# LEDPower.net
KiCad netlist of a schematic drawn in Altium Designer
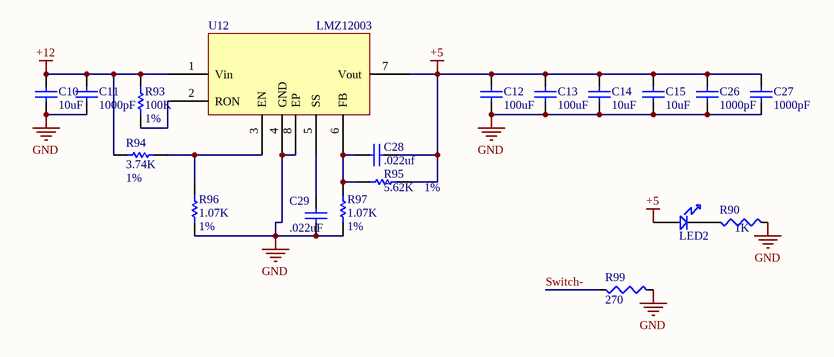
[diagram p0: LEDPower.SchDoc]

(export (version "E")
  (design (tool "Eeschema 10.0.6"))
  (components
    (comp (ref "C10")
      (value "10uF")
      (footprint "PassiveComponents:0805 (2012) Capacitor")
      (description "Capacitor")
      (libsource (lib "PassiveComponents") (part "Capacitor (non-polarized)"))
    )
    (comp (ref "C11")
      (value "1000pF")
      (footprint "PassiveComponents:0805 (2012) Capacitor")
      (description "Capacitor")
      (libsource (lib "PassiveComponents") (part "Capacitor (non-polarized)"))
    )
    (comp (ref "C12")
      (value "100uF")
      (footprint "PassiveComponents:1210 (3225) Capacitor")
      (description "Capacitor")
      (libsource (lib "PassiveComponents") (part "Capacitor (non-polarized)"))
    )
    (comp (ref "C13")
      (value "100uF")
      (footprint "PassiveComponents:1210 (3225) Capacitor")
      (description "Capacitor")
      (libsource (lib "PassiveComponents") (part "Capacitor (non-polarized)"))
    )
    (comp (ref "C14")
      (value "10uF")
      (footprint "PassiveComponents:0805 (2012) Capacitor")
      (description "Capacitor")
      (libsource (lib "PassiveComponents") (part "Capacitor (non-polarized)"))
    )
    (comp (ref "C15")
      (value "10uF")
      (footprint "PassiveComponents:0805 (2012) Capacitor")
      (description "Capacitor")
      (libsource (lib "PassiveComponents") (part "Capacitor (non-polarized)"))
    )
    (comp (ref "C26")
      (value "1000pF")
      (footprint "PassiveComponents:0805 (2012) Capacitor")
      (description "Capacitor")
      (libsource (lib "PassiveComponents") (part "Capacitor (non-polarized)"))
    )
    (comp (ref "C27")
      (value "1000pF")
      (footprint "PassiveComponents:0805 (2012) Capacitor")
      (description "Capacitor")
      (libsource (lib "PassiveComponents") (part "Capacitor (non-polarized)"))
    )
    (comp (ref "C28")
      (value ".022uf")
      (footprint "PassiveComponents:0805 (2012) Capacitor")
      (description "Capacitor")
      (libsource (lib "PassiveComponents") (part "Capacitor (non-polarized)"))
    )
    (comp (ref "C29")
      (value ".022uF")
      (footprint "PassiveComponents:0805 (2012) Capacitor")
      (description "Capacitor")
      (libsource (lib "PassiveComponents") (part "Capacitor (non-polarized)"))
    )
    (comp (ref "LED2")
      (value "LED")
      (footprint "LED 0805")
      (description "Standard LED")
      (libsource (lib "PassiveComponents") (part "LED"))
    )
    (comp (ref "R90")
      (value "1K")
      (footprint "0805 (2012) Capacitor")
      (description "Resistor")
      (libsource (lib "PassiveComponents") (part "Resistor"))
    )
    (comp (ref "R93")
      (value "100K")
      (footprint "R 0805 (2012) RESISTOR")
      (fields (field (name "TOLERANCE") "1%"))
      (libsource (lib "LEDCube") (part "RES 0805 1K 1%"))
    )
    (comp (ref "R94")
      (value "3.74K")
      (footprint "R 0805 (2012) RESISTOR")
      (fields (field (name "TOLERANCE") "1%"))
      (libsource (lib "LEDCube") (part "RES 0805 1K 1%"))
    )
    (comp (ref "R95")
      (value "5.62K")
      (footprint "R 0805 (2012) RESISTOR")
      (fields (field (name "TOLERANCE") "1%"))
      (libsource (lib "LEDCube") (part "RES 0805 1K 1%"))
    )
    (comp (ref "R96")
      (value "1.07K")
      (footprint "R 0805 (2012) RESISTOR")
      (fields (field (name "TOLERANCE") "1%"))
      (libsource (lib "LEDCube") (part "RES 0805 1K 1%"))
    )
    (comp (ref "R97")
      (value "1.07K")
      (footprint "R 0805 (2012) RESISTOR")
      (fields (field (name "TOLERANCE") "1%"))
      (libsource (lib "LEDCube") (part "RES 0805 1K 1%"))
    )
    (comp (ref "R99")
      (value "270")
      (footprint "0805 (2012) Capacitor")
      (description "Resistor")
      (libsource (lib "LEDCube") (part "Resistor"))
    )
    (comp (ref "U12")
      (value "LMZ12003")
      (footprint "7-Lead PFM")
      (libsource (lib "LEDCube") (part "LMZ12003"))
    )
  )
  (nets
    (net (code "1") (name "+5") (class "Default")
      (node (ref "C12") (pin "2") (pinfunction "2_2") (pintype "passive"))
      (node (ref "C13") (pin "2") (pinfunction "2_2") (pintype "passive"))
      (node (ref "C14") (pin "1") (pinfunction "1_1") (pintype "passive"))
      (node (ref "C15") (pin "1") (pinfunction "1_1") (pintype "passive"))
      (node (ref "C26") (pin "1") (pinfunction "1_1") (pintype "passive"))
      (node (ref "C27") (pin "1") (pinfunction "1_1") (pintype "passive"))
      (node (ref "C28") (pin "1") (pinfunction "1_1") (pintype "passive"))
      (node (ref "LED2") (pin "2") (pinfunction "2_2") (pintype "passive"))
      (node (ref "R95") (pin "1") (pinfunction "1_1") (pintype "passive"))
      (node (ref "U12") (pin "7") (pinfunction "Vout_7") (pintype "passive"))
    )
    (net (code "2") (name "+12") (class "Default")
      (node (ref "C10") (pin "2") (pinfunction "2_2") (pintype "passive"))
      (node (ref "C11") (pin "2") (pinfunction "2_2") (pintype "passive"))
      (node (ref "R93") (pin "2") (pinfunction "2_2") (pintype "passive"))
      (node (ref "R94") (pin "2") (pinfunction "2_2") (pintype "passive"))
      (node (ref "U12") (pin "1") (pinfunction "Vin_1") (pintype "passive"))
    )
    (net (code "3") (name "/Switch-") (class "Default")
      (node (ref "R99") (pin "1") (pinfunction "1_1") (pintype "passive"))
    )
    (net (code "4") (name "GND") (class "Default")
      (node (ref "C10") (pin "1") (pinfunction "1_1") (pintype "passive"))
      (node (ref "C11") (pin "1") (pinfunction "1_1") (pintype "passive"))
      (node (ref "C12") (pin "1") (pinfunction "1_1") (pintype "passive"))
      (node (ref "C13") (pin "1") (pinfunction "1_1") (pintype "passive"))
      (node (ref "C14") (pin "2") (pinfunction "2_2") (pintype "passive"))
      (node (ref "C15") (pin "2") (pinfunction "2_2") (pintype "passive"))
      (node (ref "C26") (pin "2") (pinfunction "2_2") (pintype "passive"))
      (node (ref "C27") (pin "2") (pinfunction "2_2") (pintype "passive"))
      (node (ref "C29") (pin "1") (pinfunction "1_1") (pintype "passive"))
      (node (ref "R90") (pin "2") (pinfunction "2_2") (pintype "passive"))
      (node (ref "R96") (pin "1") (pinfunction "1_1") (pintype "passive"))
      (node (ref "R97") (pin "2") (pinfunction "2_2") (pintype "passive"))
      (node (ref "R99") (pin "2") (pinfunction "2_2") (pintype "passive"))
      (node (ref "U12") (pin "4") (pinfunction "GND_4") (pintype "passive"))
      (node (ref "U12") (pin "8") (pinfunction "EP_8") (pintype "passive"))
    )
    (net (code "5") (name "Net-(LED2-Pad1)") (class "Default")
      (node (ref "LED2") (pin "1") (pinfunction "1_1") (pintype "passive"))
      (node (ref "R90") (pin "1") (pinfunction "1_1") (pintype "passive"))
    )
    (net (code "6") (name "Net-(U12-EN)") (class "Default")
      (node (ref "R94") (pin "1") (pinfunction "1_1") (pintype "passive"))
      (node (ref "R96") (pin "2") (pinfunction "2_2") (pintype "passive"))
      (node (ref "U12") (pin "3") (pinfunction "EN_3") (pintype "passive"))
    )
    (net (code "7") (name "Net-(U12-FB)") (class "Default")
      (node (ref "C28") (pin "2") (pinfunction "2_2") (pintype "passive"))
      (node (ref "R95") (pin "2") (pinfunction "2_2") (pintype "passive"))
      (node (ref "R97") (pin "1") (pinfunction "1_1") (pintype "passive"))
      (node (ref "U12") (pin "6") (pinfunction "FB_6") (pintype "passive"))
    )
    (net (code "8") (name "Net-(U12-RON)") (class "Default")
      (node (ref "R93") (pin "1") (pinfunction "1_1") (pintype "passive"))
      (node (ref "U12") (pin "2") (pinfunction "RON_2") (pintype "passive"))
    )
    (net (code "9") (name "Net-(U12-SS)") (class "Default")
      (node (ref "C29") (pin "2") (pinfunction "2_2") (pintype "passive"))
      (node (ref "U12") (pin "5") (pinfunction "SS_5") (pintype "passive"))
    )
  )
)
